# LM-CT-001.net
KiCad netlist of a schematic drawn in Altium Designer
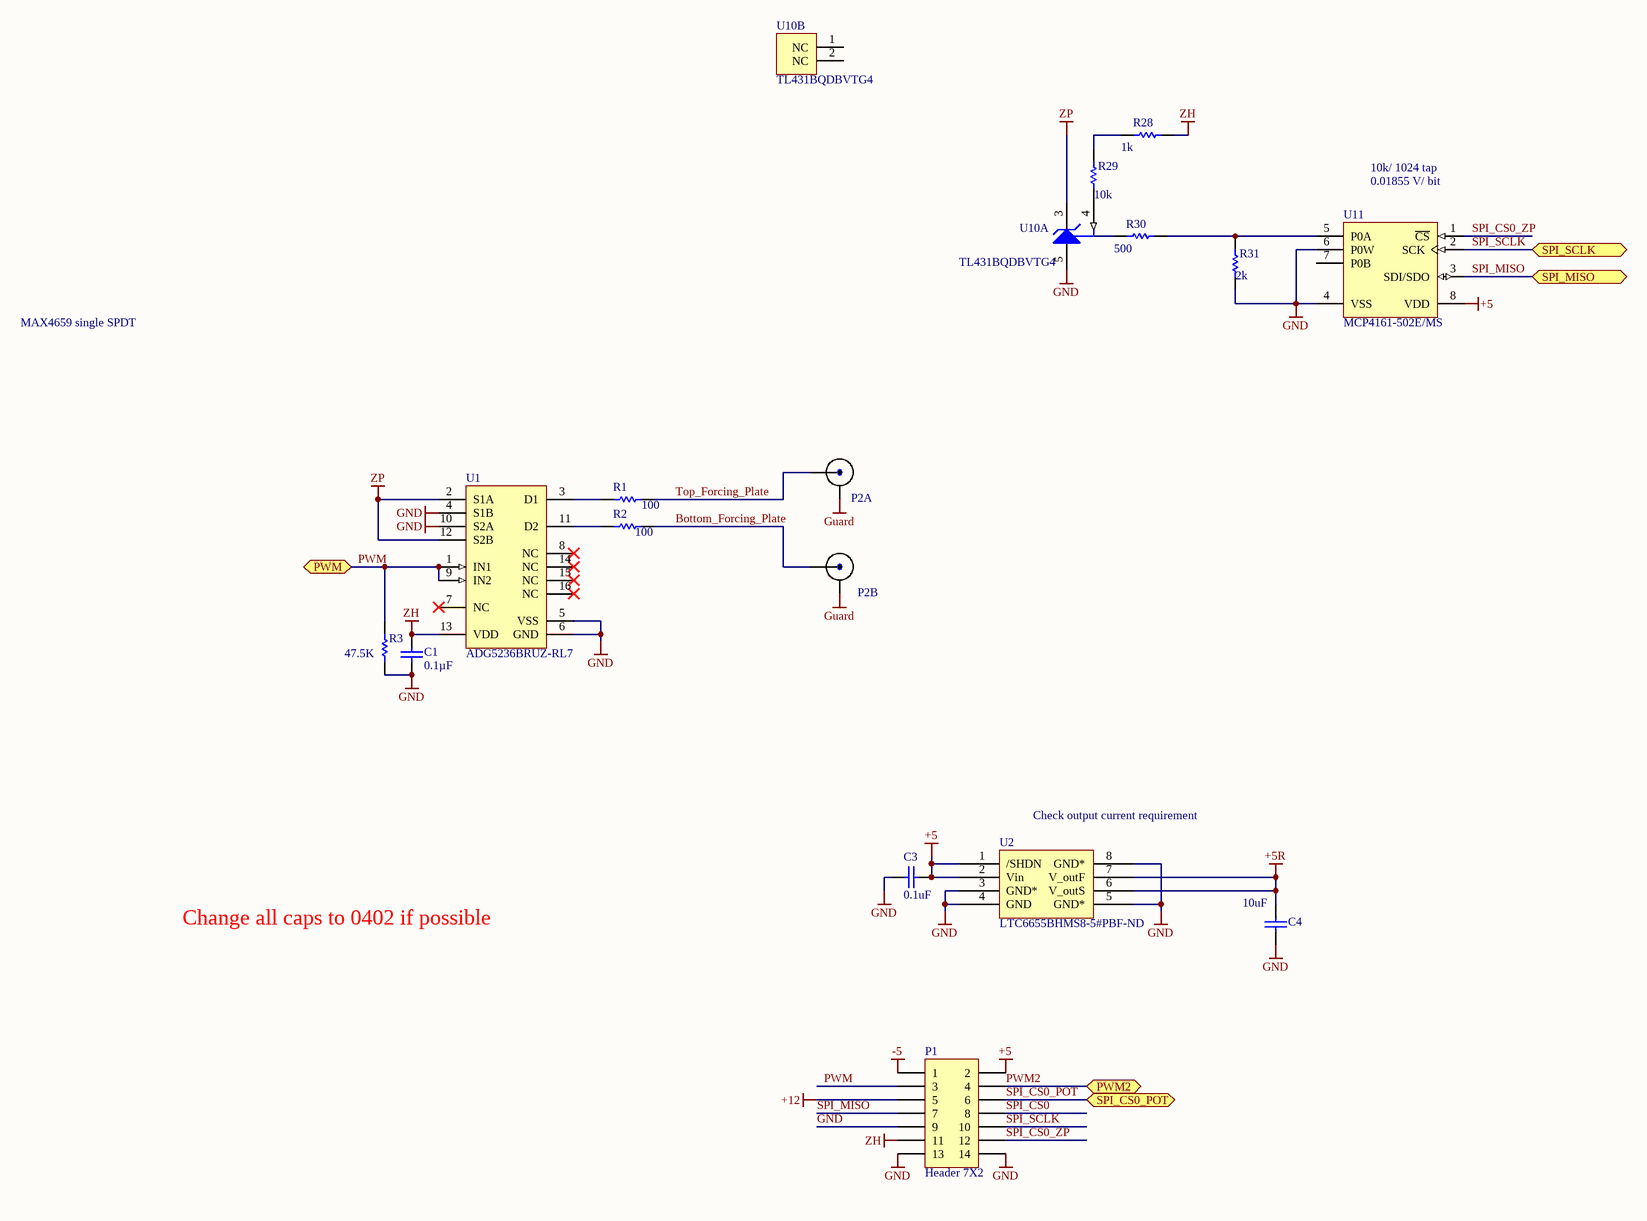
[diagram p0: LM-CT-001.SchDoc]

(export (version "E")
  (design (tool "Eeschema 10.0.6"))
  (components
    (comp (ref "C1")
      (value "CAP CER 0.1UF 25V X7R 0805")
      (footprint "CAPC0805(2012)145_N")
      (fields
        (field (name "MANUFACTURER") "Murata Electronics North America")
        (field (name "MANUFACTURER PART NUMBER") "GRM21BR71E104KA01L")
        (field (name "CAPACITANCE") "0.1µF")
        (field (name "TOLERANCE") "±10%")
      )
      (libsource (lib "Altium Content Vault") (part "CMP-1036-04795-1"))
    )
    (comp (ref "C3")
      (value "0.1uF")
      (footprint "CAPC0402(1005)60_L")
      (description "CAP CER 0.1UF 10V X7R 0402")
      (fields
        (field (name "MANUFACTURER") "Murata Electronics North America")
        (field (name "MANUFACTURER PART NUMBER") "GRM155R71A104KA01D")
      )
      (libsource (lib "Altium Content Vault") (part "CMP-1034-00252-1"))
    )
    (comp (ref "C4")
      (value "10uF")
      (footprint "CAPC1812(4532)250_N")
      (description "CAP FILM 10UF 20% 16VDC 1812")
      (fields (field (name "TOLERANCE") "Â±10%") (field (name "MANUFACTURER") "Rubycon"))
      (libsource (lib "Altium Content Vault") (part "CMP-1040-01653-1"))
    )
    (comp (ref "P1")
      (value "Header 7X2")
      (footprint "FTSH-107-01-F-D-K")
      (description "Header, 7-Pin, Dual row")
      (fields (field (name "PUBLISHER") "Altium Limited"))
      (libsource (lib "Miscellaneous Connectors") (part "Header 7X2"))
    )
    (comp (ref "P2")
      (value "GRF1-P-P-04-E-ST-TH1")
      (footprint "GRF1-P-P-04-E-ST-TH1")
      (libsource (lib "ZLS_Schematic_lib") (part "GRF1-P-P-04-E-ST-TH1"))
    )
    (comp (ref "R1")
      (value "100")
      (footprint "RESC0402(1005)_M")
      (libsource (lib "Altium Content Vault") (part "CMP-1011-00463-1"))
    )
    (comp (ref "R2")
      (value "100")
      (footprint "RESC0402(1005)_M")
      (libsource (lib "Altium Content Vault") (part "CMP-1011-00463-1"))
    )
    (comp (ref "R3")
      (value "47.5K")
      (footprint "RESC0402(1005)_M")
      (libsource (lib "Altium Content Vault") (part "CMP-1011-00463-1"))
    )
    (comp (ref "R28")
      (value "1k")
      (footprint "RESC0402(1005)_M")
      (libsource (lib "Altium Content Vault") (part "CMP-1011-00463-1"))
    )
    (comp (ref "R29")
      (value "10k")
      (footprint "RESC0402(1005)_M")
      (libsource (lib "Altium Content Vault") (part "CMP-1011-00463-1"))
    )
    (comp (ref "R30")
      (value "500")
      (footprint "RESC0402(1005)_M")
      (libsource (lib "Altium Content Vault") (part "CMP-1011-00463-1"))
    )
    (comp (ref "R31")
      (value "2k")
      (footprint "RESC0402(1005)_M")
      (libsource (lib "Altium Content Vault") (part "CMP-1011-00463-1"))
    )
    (comp (ref "U1")
      (value "ADG5236BRUZ-RL7")
      (footprint "ADI-RU-16_L")
      (description "High Voltage Latch-Up Proof, Dual SPDT Switches, 160 Ohm Ron, 16-pin SOP (RU-16), Reel")
      (fields (field (name "MANUFACTURER") "Analog Devices"))
      (libsource (lib "Altium Content Vault") (part "ADI-ADG5236-RU-16"))
    )
    (comp (ref "U2")
      (value "LTC6655BHMS8-5#PBF")
      (footprint "TSOP65P490X110-8N")
      (fields
        (field (name "SUPPLIER PART NUMBER 1") "LTC6655BHMS8-5#PBF-ND")
        (field (name "MANUFACTURER") "Linear Technology")
        (field (name "TOLERANCE") "±0.025%")
      )
      (libsource (lib "ZLS_Schematic_lib") (part "LTC6655BHMS8-5#PBF"))
    )
    (comp (ref "U10")
      (value "TL431BQDBVTG4")
      (footprint "TI-DBV5_N")
      (fields (field (name "MANUFACTURER") "Texas Instruments"))
      (libsource (lib "Altium Content Vault") (part "TI-TL431BDBV5"))
    )
    (comp (ref "U11")
      (value "MCP4161-502E/MS")
      (footprint "MSOP-MS8_N")
      (description "7/8-Bit Single/Dual SPI Digital POT with Non-Volatile Memory, 8-Pin MSOP, Extended Temperature")
      (libsource (lib "Altium Content Vault") (part "CMP-0188-00907-2"))
    )
  )
  (nets
    (net (code "1") (name "+5") (class "Default")
      (node (ref "C3") (pin "2") (pinfunction "2_2") (pintype "passive"))
      (node (ref "P1") (pin "2") (pinfunction "2_2") (pintype "passive"))
      (node (ref "U11") (pin "8") (pinfunction "VDD_8") (pintype "power_in"))
      (node (ref "U2") (pin "1") (pinfunction "/SHDN_1") (pintype "passive"))
      (node (ref "U2") (pin "2") (pinfunction "Vin_2") (pintype "passive"))
    )
    (net (code "2") (name "+5R") (class "Default")
      (node (ref "C4") (pin "2") (pinfunction "2_2") (pintype "passive"))
      (node (ref "U2") (pin "6") (pinfunction "V_outS_6") (pintype "passive"))
      (node (ref "U2") (pin "7") (pinfunction "V_outF_7") (pintype "passive"))
    )
    (net (code "3") (name "+12") (class "Default")
      (node (ref "P1") (pin "5") (pinfunction "5_5") (pintype "passive"))
    )
    (net (code "4") (name "-5") (class "Default")
      (node (ref "P1") (pin "1") (pinfunction "1_1") (pintype "passive"))
    )
    (net (code "5") (name "/Bottom_Forcing_Plate") (class "Default")
      (node (ref "P2") (pin "2") (pinfunction "2_2") (pintype "passive"))
      (node (ref "R2") (pin "1") (pinfunction "1_1") (pintype "passive"))
    )
    (net (code "6") (name "/PWM") (class "Default")
      (node (ref "P1") (pin "3") (pinfunction "3_3") (pintype "passive"))
      (node (ref "R3") (pin "1") (pinfunction "1_1") (pintype "passive"))
      (node (ref "U1") (pin "1") (pinfunction "IN1_1") (pintype "input"))
      (node (ref "U1") (pin "9") (pinfunction "IN2_9") (pintype "input"))
    )
    (net (code "7") (name "/PWM2") (class "Default")
      (node (ref "P1") (pin "4") (pinfunction "4_4") (pintype "passive"))
    )
    (net (code "8") (name "/SPI_CS0") (class "Default")
      (node (ref "P1") (pin "8") (pinfunction "8_8") (pintype "passive"))
    )
    (net (code "9") (name "/SPI_CS0_POT") (class "Default")
      (node (ref "P1") (pin "6") (pinfunction "6_6") (pintype "passive"))
    )
    (net (code "10") (name "/SPI_CS0_ZP") (class "Default")
      (node (ref "P1") (pin "12") (pinfunction "12_12") (pintype "passive"))
      (node (ref "U11") (pin "1") (pinfunction "~{CS}_1") (pintype "input"))
    )
    (net (code "11") (name "/SPI_MISO") (class "Default")
      (node (ref "P1") (pin "7") (pinfunction "7_7") (pintype "passive"))
      (node (ref "U11") (pin "3") (pinfunction "SDI/SDO_3") (pintype "bidirectional"))
    )
    (net (code "12") (name "/SPI_SCLK") (class "Default")
      (node (ref "P1") (pin "10") (pinfunction "10_10") (pintype "passive"))
      (node (ref "U11") (pin "2") (pinfunction "SCK_2") (pintype "input"))
    )
    (net (code "13") (name "/Top_Forcing_Plate") (class "Default")
      (node (ref "P2") (pin "1") (pinfunction "1_1") (pintype "passive"))
      (node (ref "R1") (pin "1") (pinfunction "1_1") (pintype "passive"))
    )
    (net (code "14") (name "GND") (class "Default")
      (node (ref "C1") (pin "1") (pinfunction "1_1") (pintype "passive"))
      (node (ref "C3") (pin "1") (pinfunction "1_1") (pintype "passive"))
      (node (ref "C4") (pin "1") (pinfunction "1_1") (pintype "passive"))
      (node (ref "P1") (pin "13") (pinfunction "13_13") (pintype "passive"))
      (node (ref "P1") (pin "14") (pinfunction "14_14") (pintype "passive"))
      (node (ref "P1") (pin "9") (pinfunction "9_9") (pintype "passive"))
      (node (ref "R3") (pin "2") (pinfunction "2_2") (pintype "passive"))
      (node (ref "R31") (pin "2") (pinfunction "2_2") (pintype "passive"))
      (node (ref "U1") (pin "10") (pinfunction "S2A_10") (pintype "passive"))
      (node (ref "U1") (pin "4") (pinfunction "S1B_4") (pintype "passive"))
      (node (ref "U1") (pin "5") (pinfunction "VSS_5") (pintype "power_in"))
      (node (ref "U1") (pin "6") (pinfunction "GND_6") (pintype "power_in"))
      (node (ref "U10") (pin "5") (pinfunction "ANODE_5") (pintype "passive"))
      (node (ref "U11") (pin "4") (pinfunction "VSS_4") (pintype "power_in"))
      (node (ref "U11") (pin "6") (pinfunction "P0W_6") (pintype "passive"))
      (node (ref "U2") (pin "3") (pinfunction "GND*_3") (pintype "passive"))
      (node (ref "U2") (pin "4") (pinfunction "GND_4") (pintype "passive"))
      (node (ref "U2") (pin "5") (pinfunction "GND*_5") (pintype "passive"))
      (node (ref "U2") (pin "8") (pinfunction "GND*_8") (pintype "passive"))
    )
    (net (code "15") (name "Guard") (class "Default")
      (node (ref "P2") (pin "7") (pinfunction "7_7") (pintype "passive"))
      (node (ref "P2") (pin "8") (pinfunction "8_8") (pintype "passive"))
    )
    (net (code "16") (name "Net-(R28-Pad1)") (class "Default")
      (node (ref "R28") (pin "1") (pinfunction "1_1") (pintype "passive"))
      (node (ref "R29") (pin "1") (pinfunction "1_1") (pintype "passive"))
    )
    (net (code "17") (name "Net-(U1-D1)") (class "Default")
      (node (ref "R1") (pin "2") (pinfunction "2_2") (pintype "passive"))
      (node (ref "U1") (pin "3") (pinfunction "D1_3") (pintype "passive"))
    )
    (net (code "18") (name "Net-(U1-D2)") (class "Default")
      (node (ref "R2") (pin "2") (pinfunction "2_2") (pintype "passive"))
      (node (ref "U1") (pin "11") (pinfunction "D2_11") (pintype "passive"))
    )
    (net (code "19") (name "Net-(U10A-REF)") (class "Default")
      (node (ref "R29") (pin "2") (pinfunction "2_2") (pintype "passive"))
      (node (ref "U10") (pin "4") (pinfunction "REF_4") (pintype "input"))
    )
    (net (code "20") (name "Net-(U11-P0A)") (class "Default")
      (node (ref "R30") (pin "2") (pinfunction "2_2") (pintype "passive"))
      (node (ref "R31") (pin "1") (pinfunction "1_1") (pintype "passive"))
      (node (ref "U11") (pin "5") (pinfunction "P0A_5") (pintype "passive"))
    )
    (net (code "21") (name "ZH") (class "Default")
      (node (ref "C1") (pin "2") (pinfunction "2_2") (pintype "passive"))
      (node (ref "P1") (pin "11") (pinfunction "11_11") (pintype "passive"))
      (node (ref "R28") (pin "2") (pinfunction "2_2") (pintype "passive"))
      (node (ref "U1") (pin "13") (pinfunction "VDD_13") (pintype "power_in"))
    )
    (net (code "22") (name "ZP") (class "Default")
      (node (ref "U1") (pin "12") (pinfunction "S2B_12") (pintype "passive"))
      (node (ref "U1") (pin "2") (pinfunction "S1A_2") (pintype "passive"))
      (node (ref "U10") (pin "3") (pinfunction "CATHODE_3") (pintype "passive"))
    )
    (net (code "23") (name "unconnected-(R30-Pad1)") (class "Default")
      (node (ref "R30") (pin "1") (pinfunction "1_1") (pintype "passive"))
    )
    (net (code "24") (name "unconnected-(U1-NC-Pad7)") (class "Default")
      (node (ref "U1") (pin "7") (pinfunction "NC_7") (pintype "passive+no_connect"))
    )
    (net (code "25") (name "unconnected-(U1-NC-Pad8)") (class "Default")
      (node (ref "U1") (pin "8") (pinfunction "NC_8") (pintype "passive+no_connect"))
    )
    (net (code "26") (name "unconnected-(U1-NC-Pad14)") (class "Default")
      (node (ref "U1") (pin "14") (pinfunction "NC_14") (pintype "passive+no_connect"))
    )
    (net (code "27") (name "unconnected-(U1-NC-Pad15)") (class "Default")
      (node (ref "U1") (pin "15") (pinfunction "NC_15") (pintype "passive+no_connect"))
    )
    (net (code "28") (name "unconnected-(U1-NC-Pad16)") (class "Default")
      (node (ref "U1") (pin "16") (pinfunction "NC_16") (pintype "passive+no_connect"))
    )
    (net (code "29") (name "unconnected-(U10B-NC-Pad1)") (class "Default")
      (node (ref "U10") (pin "1") (pinfunction "NC_1") (pintype "passive"))
    )
    (net (code "30") (name "unconnected-(U10B-NC-Pad2)") (class "Default")
      (node (ref "U10") (pin "2") (pinfunction "NC_2") (pintype "passive"))
    )
    (net (code "31") (name "unconnected-(U11-P0B-Pad7)") (class "Default")
      (node (ref "U11") (pin "7") (pinfunction "P0B_7") (pintype "passive"))
    )
  )
)
